# Raspi.net
KiCad netlist of a schematic drawn in Altium Designer
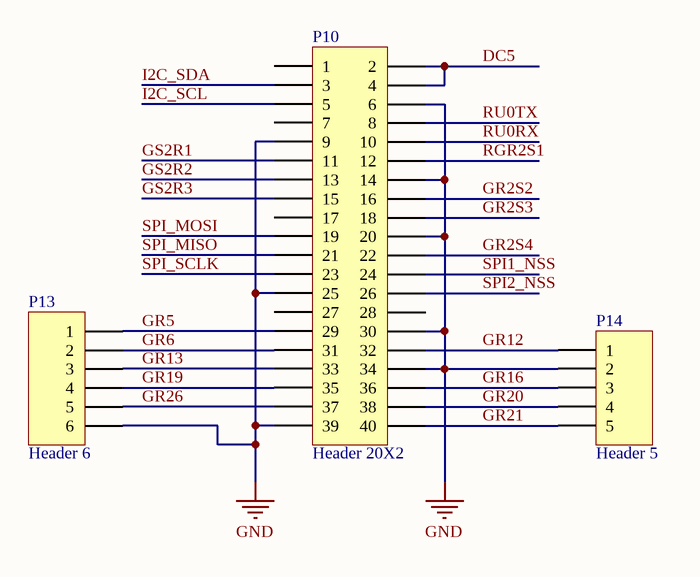
[diagram p0: Raspi.SchDoc]

(export (version "E")
  (design (tool "Eeschema 10.0.6"))
  (components
    (comp (ref "P10")
      (value "Header 20X2")
      (footprint "HDR2X20")
      (description "Header, 20-Pin, Dual row")
      (fields (field (name "PUBLISHER") "Altium Limited"))
      (libsource (lib "Miscellaneous Connectors") (part "Header 20X2"))
    )
    (comp (ref "P13")
      (value "Header 6")
      (footprint "HDR1X6")
      (description "Header, 6-Pin")
      (fields (field (name "PUBLISHER") "Altium Limited"))
      (libsource (lib "Miscellaneous Connectors") (part "Header 6"))
    )
    (comp (ref "P14")
      (value "Header 5")
      (footprint "HDR1X5")
      (description "Header, 5-Pin")
      (fields (field (name "PUBLISHER") "Altium Limited"))
      (libsource (lib "Miscellaneous Connectors") (part "Header 5"))
    )
  )
  (nets
    (net (code "1") (name "/DC5") (class "Default")
      (node (ref "P10") (pin "2") (pinfunction "2_2") (pintype "passive"))
      (node (ref "P10") (pin "4") (pinfunction "4_4") (pintype "passive"))
    )
    (net (code "2") (name "/GR2S2") (class "Default")
      (node (ref "P10") (pin "16") (pinfunction "16_16") (pintype "passive"))
    )
    (net (code "3") (name "/GR2S3") (class "Default")
      (node (ref "P10") (pin "18") (pinfunction "18_18") (pintype "passive"))
    )
    (net (code "4") (name "/GR2S4") (class "Default")
      (node (ref "P10") (pin "22") (pinfunction "22_22") (pintype "passive"))
    )
    (net (code "5") (name "/GR5") (class "Default")
      (node (ref "P10") (pin "29") (pinfunction "29_29") (pintype "passive"))
      (node (ref "P13") (pin "1") (pinfunction "1_1") (pintype "passive"))
    )
    (net (code "6") (name "/GR6") (class "Default")
      (node (ref "P10") (pin "31") (pinfunction "31_31") (pintype "passive"))
      (node (ref "P13") (pin "2") (pinfunction "2_2") (pintype "passive"))
    )
    (net (code "7") (name "/GR12") (class "Default")
      (node (ref "P10") (pin "32") (pinfunction "32_32") (pintype "passive"))
      (node (ref "P14") (pin "1") (pinfunction "1_1") (pintype "passive"))
    )
    (net (code "8") (name "/GR13") (class "Default")
      (node (ref "P10") (pin "33") (pinfunction "33_33") (pintype "passive"))
      (node (ref "P13") (pin "3") (pinfunction "3_3") (pintype "passive"))
    )
    (net (code "9") (name "/GR16") (class "Default")
      (node (ref "P10") (pin "36") (pinfunction "36_36") (pintype "passive"))
      (node (ref "P14") (pin "3") (pinfunction "3_3") (pintype "passive"))
    )
    (net (code "10") (name "/GR19") (class "Default")
      (node (ref "P10") (pin "35") (pinfunction "35_35") (pintype "passive"))
      (node (ref "P13") (pin "4") (pinfunction "4_4") (pintype "passive"))
    )
    (net (code "11") (name "/GR20") (class "Default")
      (node (ref "P10") (pin "38") (pinfunction "38_38") (pintype "passive"))
      (node (ref "P14") (pin "4") (pinfunction "4_4") (pintype "passive"))
    )
    (net (code "12") (name "/GR21") (class "Default")
      (node (ref "P10") (pin "40") (pinfunction "40_40") (pintype "passive"))
      (node (ref "P14") (pin "5") (pinfunction "5_5") (pintype "passive"))
    )
    (net (code "13") (name "/GR26") (class "Default")
      (node (ref "P10") (pin "37") (pinfunction "37_37") (pintype "passive"))
      (node (ref "P13") (pin "5") (pinfunction "5_5") (pintype "passive"))
    )
    (net (code "14") (name "/GS2R1") (class "Default")
      (node (ref "P10") (pin "11") (pinfunction "11_11") (pintype "passive"))
    )
    (net (code "15") (name "/GS2R2") (class "Default")
      (node (ref "P10") (pin "13") (pinfunction "13_13") (pintype "passive"))
    )
    (net (code "16") (name "/GS2R3") (class "Default")
      (node (ref "P10") (pin "15") (pinfunction "15_15") (pintype "passive"))
    )
    (net (code "17") (name "/I2C_SCL") (class "Default")
      (node (ref "P10") (pin "5") (pinfunction "5_5") (pintype "passive"))
    )
    (net (code "18") (name "/I2C_SDA") (class "Default")
      (node (ref "P10") (pin "3") (pinfunction "3_3") (pintype "passive"))
    )
    (net (code "19") (name "/RGR2S1") (class "Default")
      (node (ref "P10") (pin "12") (pinfunction "12_12") (pintype "passive"))
    )
    (net (code "20") (name "/RU0RX") (class "Default")
      (node (ref "P10") (pin "10") (pinfunction "10_10") (pintype "passive"))
    )
    (net (code "21") (name "/RU0TX") (class "Default")
      (node (ref "P10") (pin "8") (pinfunction "8_8") (pintype "passive"))
    )
    (net (code "22") (name "/SPI1_NSS") (class "Default")
      (node (ref "P10") (pin "24") (pinfunction "24_24") (pintype "passive"))
    )
    (net (code "23") (name "/SPI2_NSS") (class "Default")
      (node (ref "P10") (pin "26") (pinfunction "26_26") (pintype "passive"))
    )
    (net (code "24") (name "/SPI_MISO") (class "Default")
      (node (ref "P10") (pin "21") (pinfunction "21_21") (pintype "passive"))
    )
    (net (code "25") (name "/SPI_MOSI") (class "Default")
      (node (ref "P10") (pin "19") (pinfunction "19_19") (pintype "passive"))
    )
    (net (code "26") (name "/SPI_SCLK") (class "Default")
      (node (ref "P10") (pin "23") (pinfunction "23_23") (pintype "passive"))
    )
    (net (code "27") (name "GND") (class "Default")
      (node (ref "P10") (pin "14") (pinfunction "14_14") (pintype "passive"))
      (node (ref "P10") (pin "20") (pinfunction "20_20") (pintype "passive"))
      (node (ref "P10") (pin "25") (pinfunction "25_25") (pintype "passive"))
      (node (ref "P10") (pin "30") (pinfunction "30_30") (pintype "passive"))
      (node (ref "P10") (pin "34") (pinfunction "34_34") (pintype "passive"))
      (node (ref "P10") (pin "39") (pinfunction "39_39") (pintype "passive"))
      (node (ref "P10") (pin "6") (pinfunction "6_6") (pintype "passive"))
      (node (ref "P10") (pin "9") (pinfunction "9_9") (pintype "passive"))
      (node (ref "P13") (pin "6") (pinfunction "6_6") (pintype "passive"))
      (node (ref "P14") (pin "2") (pinfunction "2_2") (pintype "passive"))
    )
    (net (code "28") (name "unconnected-(P10-Pad1)") (class "Default")
      (node (ref "P10") (pin "1") (pinfunction "1_1") (pintype "passive"))
    )
    (net (code "29") (name "unconnected-(P10-Pad7)") (class "Default")
      (node (ref "P10") (pin "7") (pinfunction "7_7") (pintype "passive"))
    )
    (net (code "30") (name "unconnected-(P10-Pad17)") (class "Default")
      (node (ref "P10") (pin "17") (pinfunction "17_17") (pintype "passive"))
    )
    (net (code "31") (name "unconnected-(P10-Pad27)") (class "Default")
      (node (ref "P10") (pin "27") (pinfunction "27_27") (pintype "passive"))
    )
    (net (code "32") (name "unconnected-(P10-Pad28)") (class "Default")
      (node (ref "P10") (pin "28") (pinfunction "28_28") (pintype "passive"))
    )
  )
)
